# current_signal_adaptation_2.net
KiCad netlist of a schematic drawn in Altium Designer
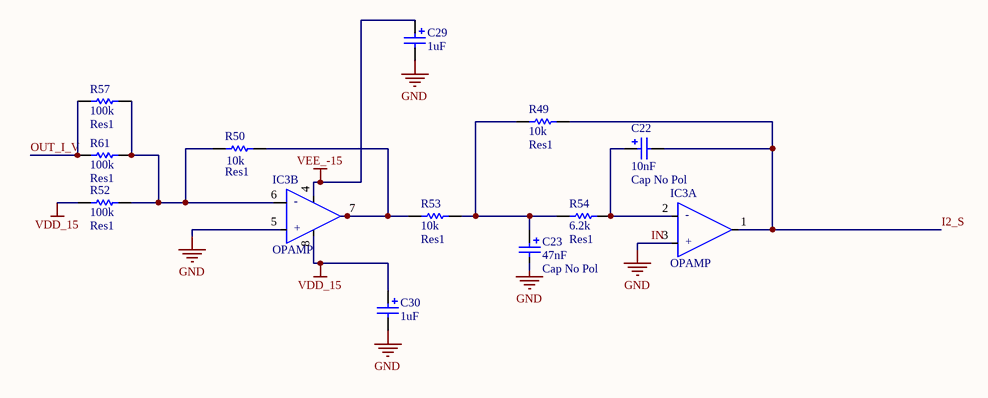
[diagram p0: current_signal_adaptation_2.SchDoc]

(export (version "E")
  (design (tool "Eeschema 10.0.6"))
  (components
    (comp (ref "C22")
      (value "Cap No Pol")
      (footprint "RAD-0.1")
      (description "Polarized Capacitor (Radial)")
      (fields (field (name "ALTIUM_VALUE") "10nF") (field (name "PUBLISHER") "Altium Limited"))
      (libsource (lib "LABSTEPS_Project") (part "Cap No Pol"))
    )
    (comp (ref "C23")
      (value "Cap No Pol")
      (footprint "RAD-0.1")
      (description "Polarized Capacitor (Radial)")
      (fields (field (name "ALTIUM_VALUE") "47nF") (field (name "PUBLISHER") "Altium Limited"))
      (libsource (lib "LABSTEPS_Project") (part "Cap No Pol"))
    )
    (comp (ref "C29")
      (value "1uF")
      (footprint "RAD-0.1")
      (description "Polarized Capacitor (Radial)")
      (fields (field (name "Comment") "Cap No Pol") (field (name "PUBLISHER") "Altium Limited"))
      (libsource (lib "LABSTEPS_Project") (part "Cap No Pol"))
    )
    (comp (ref "C30")
      (value "1uF")
      (footprint "RAD-0.1")
      (description "Polarized Capacitor (Radial)")
      (fields (field (name "Comment") "Cap No Pol") (field (name "PUBLISHER") "Altium Limited"))
      (libsource (lib "LABSTEPS_Project") (part "Cap No Pol"))
    )
    (comp (ref "IC3")
      (value "OPAMP")
      (footprint "DIP-8")
      (description "ADTL082")
      (libsource (lib "LABSTEPS_Project") (part "ADTL082"))
    )
    (comp (ref "R49")
      (value "Res1")
      (footprint "AXIAL-0.4")
      (description "Resistor")
      (fields (field (name "ALTIUM_VALUE") "10k") (field (name "PUBLISHER") "Altium Limited"))
      (libsource (lib "LABSTEPS_Project") (part "Res1"))
    )
    (comp (ref "R50")
      (value "Res1")
      (footprint "AXIAL-0.4")
      (description "Resistor")
      (fields (field (name "ALTIUM_VALUE") "10k") (field (name "PUBLISHER") "Altium Limited"))
      (libsource (lib "LABSTEPS_Project") (part "Res1"))
    )
    (comp (ref "R52")
      (value "Res1")
      (footprint "AXIAL-0.4")
      (description "Resistor")
      (fields (field (name "ALTIUM_VALUE") "100k") (field (name "PUBLISHER") "Altium Limited"))
      (libsource (lib "LABSTEPS_Project") (part "Res1"))
    )
    (comp (ref "R53")
      (value "Res1")
      (footprint "AXIAL-0.4")
      (description "Resistor")
      (fields (field (name "ALTIUM_VALUE") "10k") (field (name "PUBLISHER") "Altium Limited"))
      (libsource (lib "LABSTEPS_Project") (part "Res1"))
    )
    (comp (ref "R54")
      (value "Res1")
      (footprint "AXIAL-0.4")
      (description "Resistor")
      (fields (field (name "ALTIUM_VALUE") "6.2k") (field (name "PUBLISHER") "Altium Limited"))
      (libsource (lib "LABSTEPS_Project") (part "Res1"))
    )
    (comp (ref "R57")
      (value "Res1")
      (footprint "AXIAL-0.4")
      (description "Resistor")
      (fields (field (name "ALTIUM_VALUE") "100k") (field (name "PUBLISHER") "Altium Limited"))
      (libsource (lib "LABSTEPS_Project") (part "Res1"))
    )
    (comp (ref "R61")
      (value "Res1")
      (footprint "AXIAL-0.4")
      (description "Resistor")
      (fields (field (name "ALTIUM_VALUE") "100k") (field (name "PUBLISHER") "Altium Limited"))
      (libsource (lib "LABSTEPS_Project") (part "Res1"))
    )
  )
  (nets
    (net (code "1") (name "/I2_S") (class "Default")
      (node (ref "C22") (pin "2") (pinfunction "2_2") (pintype "passive"))
      (node (ref "IC3") (pin "1") (pinfunction "OUT_A_1") (pintype "passive"))
      (node (ref "R49") (pin "2") (pinfunction "2_2") (pintype "passive"))
    )
    (net (code "2") (name "/OUT_I_V") (class "Default")
      (node (ref "R57") (pin "1") (pinfunction "1_1") (pintype "passive"))
      (node (ref "R61") (pin "1") (pinfunction "1_1") (pintype "passive"))
    )
    (net (code "3") (name "GND") (class "Default")
      (node (ref "C23") (pin "2") (pinfunction "2_2") (pintype "passive"))
      (node (ref "C29") (pin "2") (pinfunction "2_2") (pintype "passive"))
      (node (ref "C30") (pin "2") (pinfunction "2_2") (pintype "passive"))
      (node (ref "IC3") (pin "3") (pinfunction "IN_A_+_3") (pintype "passive"))
      (node (ref "IC3") (pin "5") (pinfunction "IN_B_+_5") (pintype "passive"))
    )
    (net (code "4") (name "Net-(C23-Pad1)") (class "Default")
      (node (ref "C23") (pin "1") (pinfunction "1_1") (pintype "passive"))
      (node (ref "R49") (pin "1") (pinfunction "1_1") (pintype "passive"))
      (node (ref "R53") (pin "2") (pinfunction "2_2") (pintype "passive"))
      (node (ref "R54") (pin "1") (pinfunction "1_1") (pintype "passive"))
    )
    (net (code "5") (name "Net-(IC3A-IN_A_-)") (class "Default")
      (node (ref "C22") (pin "1") (pinfunction "1_1") (pintype "passive"))
      (node (ref "IC3") (pin "2") (pinfunction "IN_A_-_2") (pintype "passive"))
      (node (ref "R54") (pin "2") (pinfunction "2_2") (pintype "passive"))
    )
    (net (code "6") (name "Net-(IC3B-OUT_B)") (class "Default")
      (node (ref "IC3") (pin "7") (pinfunction "OUT_B_7") (pintype "passive"))
      (node (ref "R50") (pin "2") (pinfunction "2_2") (pintype "passive"))
      (node (ref "R53") (pin "1") (pinfunction "1_1") (pintype "passive"))
    )
    (net (code "7") (name "Net-(R50-Pad1)") (class "Default")
      (node (ref "R50") (pin "1") (pinfunction "1_1") (pintype "passive"))
      (node (ref "R52") (pin "2") (pinfunction "2_2") (pintype "passive"))
      (node (ref "R57") (pin "2") (pinfunction "2_2") (pintype "passive"))
      (node (ref "R61") (pin "2") (pinfunction "2_2") (pintype "passive"))
    )
    (net (code "8") (name "VDD_15") (class "Default")
      (node (ref "C30") (pin "1") (pinfunction "1_1") (pintype "passive"))
      (node (ref "IC3") (pin "8") (pinfunction "V+_8") (pintype "passive"))
      (node (ref "R52") (pin "1") (pinfunction "1_1") (pintype "passive"))
    )
    (net (code "9") (name "VEE_-15") (class "Default")
      (node (ref "C29") (pin "1") (pinfunction "1_1") (pintype "passive"))
      (node (ref "IC3") (pin "4") (pinfunction "-V_4") (pintype "passive"))
    )
    (net (code "10") (name "unconnected-(IC3B-IN_B_--Pad6)") (class "Default")
      (node (ref "IC3") (pin "6") (pinfunction "IN_B_-_6") (pintype "passive"))
    )
  )
)
